# PCI_da_FPGA.net
KiCad netlist of a schematic drawn in EAGLE
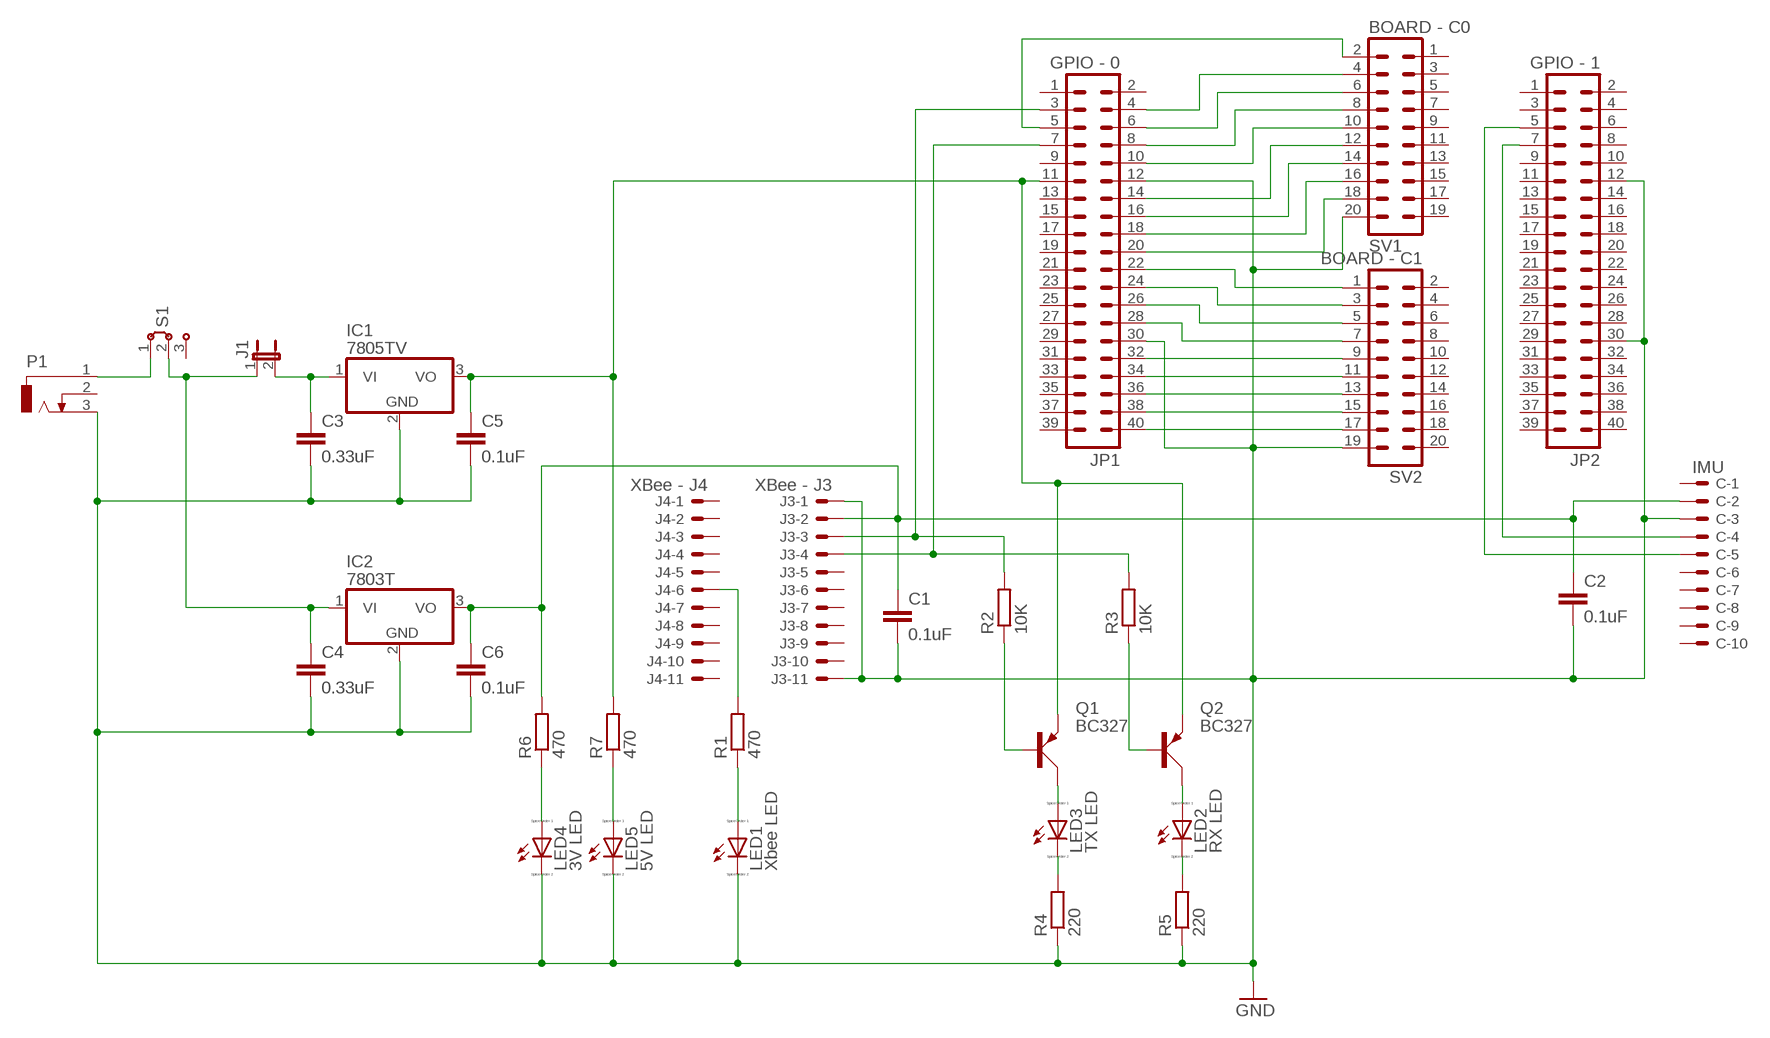
[diagram p0: schematic, sheet 1]

(export (version "E")
  (design (tool "Eeschema 10.0.6"))
  (components
    (comp (ref "C")
      (value "IMU")
      (footprint "eagle-import:22-23-2101")
      (fields (field (name "MF") "MOLEX") (field (name "MPN") "22-23-2101"))
      (libsource (lib "eagle-import") (part "22-23-2101"))
    )
    (comp (ref "C1")
      (value "0.1uF")
      (footprint "eagle-import:C5B2.5")
      (libsource (lib "eagle-import") (part "C5/2.5"))
    )
    (comp (ref "C2")
      (value "0.1uF")
      (footprint "eagle-import:C5B2.5")
      (libsource (lib "eagle-import") (part "C5/2.5"))
    )
    (comp (ref "C3")
      (value "0.33uF")
      (footprint "eagle-import:C5B2.5")
      (libsource (lib "eagle-import") (part "C5/2.5"))
    )
    (comp (ref "C4")
      (value "0.33uF")
      (footprint "eagle-import:C5B2.5")
      (libsource (lib "eagle-import") (part "C5/2.5"))
    )
    (comp (ref "C5")
      (value "0.1uF")
      (footprint "eagle-import:C5B2.5")
      (libsource (lib "eagle-import") (part "C5/2.5"))
    )
    (comp (ref "C6")
      (value "0.1uF")
      (footprint "eagle-import:C5B2.5")
      (libsource (lib "eagle-import") (part "C5/2.5"))
    )
    (comp (ref "IC1")
      (value "7805TV")
      (footprint "eagle-import:TO220V")
      (libsource (lib "eagle-import") (part "78TV05"))
    )
    (comp (ref "IC2")
      (value "7803T")
      (footprint "eagle-import:TO220V")
      (libsource (lib "eagle-import") (part "78TV05"))
    )
    (comp (ref "J1")
      (value "JP1E")
      (footprint "eagle-import:JP1")
      (libsource (lib "eagle-import") (part "JP1E"))
    )
    (comp (ref "J3")
      (value "XBee - J3")
      (footprint "eagle-import:22-23-2111")
      (fields (field (name "MF") "MOLEX") (field (name "MPN") "22-23-2111"))
      (libsource (lib "eagle-import") (part "22-23-2111"))
    )
    (comp (ref "J4")
      (value "XBee - J4")
      (footprint "eagle-import:22-23-2111")
      (fields (field (name "MF") "MOLEX") (field (name "MPN") "22-23-2111"))
      (libsource (lib "eagle-import") (part "22-23-2111"))
    )
    (comp (ref "JP1")
      (value "GPIO - 0")
      (footprint "eagle-import:ML40")
      (libsource (lib "eagle-import") (part "ML40"))
    )
    (comp (ref "JP2")
      (value "GPIO - 1")
      (footprint "eagle-import:ML40")
      (libsource (lib "eagle-import") (part "ML40"))
    )
    (comp (ref "LED1")
      (value "Xbee LED")
      (footprint "eagle-import:LED_LD260")
      (libsource (lib "eagle-import") (part "LED_ELD260"))
    )
    (comp (ref "LED2")
      (value "RX LED")
      (footprint "eagle-import:LED_LD260")
      (libsource (lib "eagle-import") (part "LED_ELD260"))
    )
    (comp (ref "LED3")
      (value "TX LED")
      (footprint "eagle-import:LED_LD260")
      (libsource (lib "eagle-import") (part "LED_ELD260"))
    )
    (comp (ref "LED4")
      (value "3V LED")
      (footprint "eagle-import:LED_LD260")
      (libsource (lib "eagle-import") (part "LED_ELD260"))
    )
    (comp (ref "LED5")
      (value "5V LED")
      (footprint "eagle-import:LED_LD260")
      (libsource (lib "eagle-import") (part "LED_ELD260"))
    )
    (comp (ref "P1")
      (value "DCJ0303")
      (footprint "eagle-import:DCJ0303")
      (libsource (lib "eagle-import") (part "DCJ0303"))
    )
    (comp (ref "Q1")
      (value "BC327")
      (footprint "eagle-import:SOT54A")
      (libsource (lib "eagle-import") (part "BC327"))
    )
    (comp (ref "Q2")
      (value "BC327")
      (footprint "eagle-import:SOT54A")
      (libsource (lib "eagle-import") (part "BC327"))
    )
    (comp (ref "R1")
      (value "470")
      (footprint "eagle-import:0207_10")
      (libsource (lib "eagle-import") (part "R-EU_0207/10"))
    )
    (comp (ref "R2")
      (value "10K")
      (footprint "eagle-import:0207_10")
      (libsource (lib "eagle-import") (part "R-EU_0207/10"))
    )
    (comp (ref "R3")
      (value "10K")
      (footprint "eagle-import:0207_10")
      (libsource (lib "eagle-import") (part "R-EU_0207/10"))
    )
    (comp (ref "R4")
      (value "220")
      (footprint "eagle-import:0207_10")
      (libsource (lib "eagle-import") (part "R-EU_0207/10"))
    )
    (comp (ref "R5")
      (value "220")
      (footprint "eagle-import:0207_10")
      (libsource (lib "eagle-import") (part "R-EU_0207/10"))
    )
    (comp (ref "R6")
      (value "470")
      (footprint "eagle-import:0207_10")
      (libsource (lib "eagle-import") (part "R-EU_0207/10"))
    )
    (comp (ref "R7")
      (value "470")
      (footprint "eagle-import:0207_10")
      (libsource (lib "eagle-import") (part "R-EU_0207/10"))
    )
    (comp (ref "S1")
      (value "J2X2MM")
      (footprint "eagle-import:04C")
      (libsource (lib "eagle-import") (part "J2X2MM"))
    )
    (comp (ref "SV1")
      (value "BOARD - C0")
      (footprint "eagle-import:ML20")
      (fields (field (name "OC_FARNELL") "unknown") (field (name "OC_NEWARK") "unknown"))
      (libsource (lib "eagle-import") (part "ML20"))
    )
    (comp (ref "SV2")
      (value "BOARD - C1")
      (footprint "eagle-import:ML20")
      (libsource (lib "eagle-import") (part "ML20"))
    )
  )
  (nets
    (net (code "1") (name "GND") (class "Default")
      (node (ref "C") (pin "3") (pinfunction "S_3") (pintype "passive"))
      (node (ref "C1") (pin "2") (pinfunction "2_2") (pintype "passive"))
      (node (ref "C2") (pin "2") (pinfunction "2_2") (pintype "passive"))
      (node (ref "C3") (pin "2") (pinfunction "2_2") (pintype "passive"))
      (node (ref "C4") (pin "2") (pinfunction "2_2") (pintype "passive"))
      (node (ref "C5") (pin "2") (pinfunction "2_2") (pintype "passive"))
      (node (ref "C6") (pin "2") (pinfunction "2_2") (pintype "passive"))
      (node (ref "IC1") (pin "2") (pinfunction "GND_2") (pintype "passive"))
      (node (ref "IC2") (pin "2") (pinfunction "GND_2") (pintype "passive"))
      (node (ref "J3") (pin "1") (pinfunction "S_1") (pintype "passive"))
      (node (ref "J3") (pin "11") (pinfunction "S_11") (pintype "passive"))
      (node (ref "JP1") (pin "12") (pinfunction "12_12") (pintype "passive"))
      (node (ref "JP1") (pin "30") (pinfunction "30_30") (pintype "passive"))
      (node (ref "JP2") (pin "12") (pinfunction "12_12") (pintype "passive"))
      (node (ref "JP2") (pin "30") (pinfunction "30_30") (pintype "passive"))
      (node (ref "LED1") (pin "K") (pinfunction "C_K") (pintype "passive"))
      (node (ref "LED4") (pin "K") (pinfunction "C_K") (pintype "passive"))
      (node (ref "LED5") (pin "K") (pinfunction "C_K") (pintype "passive"))
      (node (ref "P1") (pin "3") (pinfunction "3_3") (pintype "passive"))
      (node (ref "R4") (pin "1") (pinfunction "1_1") (pintype "passive"))
      (node (ref "R5") (pin "1") (pinfunction "1_1") (pintype "passive"))
      (node (ref "SV1") (pin "20") (pinfunction "20_20") (pintype "passive"))
      (node (ref "SV2") (pin "19") (pinfunction "19_19") (pintype "passive"))
    )
    (net (code "2") (name "Net-(CC-S)") (class "Default")
      (node (ref "C") (pin "2") (pinfunction "S_2") (pintype "passive"))
      (node (ref "C1") (pin "1") (pinfunction "1_1") (pintype "passive"))
      (node (ref "C2") (pin "1") (pinfunction "1_1") (pintype "passive"))
      (node (ref "C6") (pin "1") (pinfunction "1_1") (pintype "passive"))
      (node (ref "IC2") (pin "3") (pinfunction "VO_3") (pintype "passive"))
      (node (ref "J3") (pin "2") (pinfunction "S_2") (pintype "passive"))
      (node (ref "R6") (pin "2") (pinfunction "2_2") (pintype "passive"))
    )
    (net (code "3") (name "Net-(CE-S)") (class "Default")
      (node (ref "C") (pin "4") (pinfunction "S_4") (pintype "passive"))
      (node (ref "JP2") (pin "7") (pinfunction "7_7") (pintype "passive"))
    )
    (net (code "4") (name "Net-(CF-S)") (class "Default")
      (node (ref "C") (pin "5") (pinfunction "S_5") (pintype "passive"))
      (node (ref "JP2") (pin "5") (pinfunction "5_5") (pintype "passive"))
    )
    (net (code "5") (name "Net-(IC1-VI)") (class "Default")
      (node (ref "C3") (pin "1") (pinfunction "1_1") (pintype "passive"))
      (node (ref "IC1") (pin "1") (pinfunction "VI_1") (pintype "input"))
      (node (ref "J1") (pin "2") (pinfunction "2_2") (pintype "passive"))
    )
    (net (code "6") (name "Net-(IC1-VO)") (class "Default")
      (node (ref "C5") (pin "1") (pinfunction "1_1") (pintype "passive"))
      (node (ref "IC1") (pin "3") (pinfunction "VO_3") (pintype "passive"))
      (node (ref "JP1") (pin "11") (pinfunction "11_11") (pintype "passive"))
      (node (ref "Q1") (pin "E") (pinfunction "E_E") (pintype "passive"))
      (node (ref "Q2") (pin "E") (pinfunction "E_E") (pintype "passive"))
      (node (ref "R7") (pin "2") (pinfunction "2_2") (pintype "passive"))
    )
    (net (code "7") (name "Net-(IC2-VI)") (class "Default")
      (node (ref "C4") (pin "1") (pinfunction "1_1") (pintype "passive"))
      (node (ref "IC2") (pin "1") (pinfunction "VI_1") (pintype "input"))
      (node (ref "J1") (pin "1") (pinfunction "1_1") (pintype "passive"))
      (node (ref "S1") (pin "2") (pinfunction "2_2") (pintype "passive"))
    )
    (net (code "8") (name "Net-(J3E-S)") (class "Default")
      (node (ref "J3") (pin "3") (pinfunction "S_3") (pintype "passive"))
      (node (ref "JP1") (pin "3") (pinfunction "3_3") (pintype "passive"))
      (node (ref "R2") (pin "2") (pinfunction "2_2") (pintype "passive"))
    )
    (net (code "9") (name "Net-(J3F-S)") (class "Default")
      (node (ref "J3") (pin "4") (pinfunction "S_4") (pintype "passive"))
      (node (ref "JP1") (pin "7") (pinfunction "7_7") (pintype "passive"))
      (node (ref "R3") (pin "2") (pinfunction "2_2") (pintype "passive"))
    )
    (net (code "10") (name "Net-(J4H-S)") (class "Default")
      (node (ref "J4") (pin "6") (pinfunction "S_6") (pintype "passive"))
      (node (ref "R1") (pin "2") (pinfunction "2_2") (pintype "passive"))
    )
    (net (code "11") (name "Net-(JP1-Pad4)") (class "Default")
      (node (ref "JP1") (pin "4") (pinfunction "4_4") (pintype "passive"))
      (node (ref "SV1") (pin "4") (pinfunction "4_4") (pintype "passive"))
    )
    (net (code "12") (name "Net-(JP1-Pad5)") (class "Default")
      (node (ref "JP1") (pin "5") (pinfunction "5_5") (pintype "passive"))
      (node (ref "SV1") (pin "2") (pinfunction "2_2") (pintype "passive"))
    )
    (net (code "13") (name "Net-(JP1-Pad6)") (class "Default")
      (node (ref "JP1") (pin "6") (pinfunction "6_6") (pintype "passive"))
      (node (ref "SV1") (pin "6") (pinfunction "6_6") (pintype "passive"))
    )
    (net (code "14") (name "Net-(JP1-Pad8)") (class "Default")
      (node (ref "JP1") (pin "8") (pinfunction "8_8") (pintype "passive"))
      (node (ref "SV1") (pin "8") (pinfunction "8_8") (pintype "passive"))
    )
    (net (code "15") (name "Net-(JP1-Pad10)") (class "Default")
      (node (ref "JP1") (pin "10") (pinfunction "10_10") (pintype "passive"))
      (node (ref "SV1") (pin "10") (pinfunction "10_10") (pintype "passive"))
    )
    (net (code "16") (name "Net-(JP1-Pad14)") (class "Default")
      (node (ref "JP1") (pin "14") (pinfunction "14_14") (pintype "passive"))
      (node (ref "SV1") (pin "12") (pinfunction "12_12") (pintype "passive"))
    )
    (net (code "17") (name "Net-(JP1-Pad16)") (class "Default")
      (node (ref "JP1") (pin "16") (pinfunction "16_16") (pintype "passive"))
      (node (ref "SV1") (pin "14") (pinfunction "14_14") (pintype "passive"))
    )
    (net (code "18") (name "Net-(JP1-Pad18)") (class "Default")
      (node (ref "JP1") (pin "18") (pinfunction "18_18") (pintype "passive"))
      (node (ref "SV1") (pin "16") (pinfunction "16_16") (pintype "passive"))
    )
    (net (code "19") (name "Net-(JP1-Pad20)") (class "Default")
      (node (ref "JP1") (pin "20") (pinfunction "20_20") (pintype "passive"))
      (node (ref "SV1") (pin "18") (pinfunction "18_18") (pintype "passive"))
    )
    (net (code "20") (name "Net-(JP1-Pad22)") (class "Default")
      (node (ref "JP1") (pin "22") (pinfunction "22_22") (pintype "passive"))
      (node (ref "SV2") (pin "1") (pinfunction "1_1") (pintype "passive"))
    )
    (net (code "21") (name "Net-(JP1-Pad24)") (class "Default")
      (node (ref "JP1") (pin "24") (pinfunction "24_24") (pintype "passive"))
      (node (ref "SV2") (pin "3") (pinfunction "3_3") (pintype "passive"))
    )
    (net (code "22") (name "Net-(JP1-Pad26)") (class "Default")
      (node (ref "JP1") (pin "26") (pinfunction "26_26") (pintype "passive"))
      (node (ref "SV2") (pin "5") (pinfunction "5_5") (pintype "passive"))
    )
    (net (code "23") (name "Net-(JP1-Pad28)") (class "Default")
      (node (ref "JP1") (pin "28") (pinfunction "28_28") (pintype "passive"))
      (node (ref "SV2") (pin "7") (pinfunction "7_7") (pintype "passive"))
    )
    (net (code "24") (name "Net-(JP1-Pad32)") (class "Default")
      (node (ref "JP1") (pin "32") (pinfunction "32_32") (pintype "passive"))
      (node (ref "SV2") (pin "9") (pinfunction "9_9") (pintype "passive"))
    )
    (net (code "25") (name "Net-(JP1-Pad34)") (class "Default")
      (node (ref "JP1") (pin "34") (pinfunction "34_34") (pintype "passive"))
      (node (ref "SV2") (pin "11") (pinfunction "11_11") (pintype "passive"))
    )
    (net (code "26") (name "Net-(JP1-Pad36)") (class "Default")
      (node (ref "JP1") (pin "36") (pinfunction "36_36") (pintype "passive"))
      (node (ref "SV2") (pin "13") (pinfunction "13_13") (pintype "passive"))
    )
    (net (code "27") (name "Net-(JP1-Pad38)") (class "Default")
      (node (ref "JP1") (pin "38") (pinfunction "38_38") (pintype "passive"))
      (node (ref "SV2") (pin "15") (pinfunction "15_15") (pintype "passive"))
    )
    (net (code "28") (name "Net-(JP1-Pad40)") (class "Default")
      (node (ref "JP1") (pin "40") (pinfunction "40_40") (pintype "passive"))
      (node (ref "SV2") (pin "17") (pinfunction "17_17") (pintype "passive"))
    )
    (net (code "29") (name "Net-(LED1-PadA)") (class "Default")
      (node (ref "LED1") (pin "A") (pinfunction "A_A") (pintype "passive"))
      (node (ref "R1") (pin "1") (pinfunction "1_1") (pintype "passive"))
    )
    (net (code "30") (name "Net-(LED2-C)") (class "Default")
      (node (ref "LED2") (pin "K") (pinfunction "C_K") (pintype "passive"))
      (node (ref "R5") (pin "2") (pinfunction "2_2") (pintype "passive"))
    )
    (net (code "31") (name "Net-(LED2-PadA)") (class "Default")
      (node (ref "LED2") (pin "A") (pinfunction "A_A") (pintype "passive"))
      (node (ref "Q2") (pin "C") (pinfunction "C_C") (pintype "passive"))
    )
    (net (code "32") (name "Net-(LED3-C)") (class "Default")
      (node (ref "LED3") (pin "K") (pinfunction "C_K") (pintype "passive"))
      (node (ref "R4") (pin "2") (pinfunction "2_2") (pintype "passive"))
    )
    (net (code "33") (name "Net-(LED3-PadA)") (class "Default")
      (node (ref "LED3") (pin "A") (pinfunction "A_A") (pintype "passive"))
      (node (ref "Q1") (pin "C") (pinfunction "C_C") (pintype "passive"))
    )
    (net (code "34") (name "Net-(LED4-PadA)") (class "Default")
      (node (ref "LED4") (pin "A") (pinfunction "A_A") (pintype "passive"))
      (node (ref "R6") (pin "1") (pinfunction "1_1") (pintype "passive"))
    )
    (net (code "35") (name "Net-(LED5-PadA)") (class "Default")
      (node (ref "LED5") (pin "A") (pinfunction "A_A") (pintype "passive"))
      (node (ref "R7") (pin "1") (pinfunction "1_1") (pintype "passive"))
    )
    (net (code "36") (name "Net-(P1-Pad1)") (class "Default")
      (node (ref "P1") (pin "1") (pinfunction "1_1") (pintype "passive"))
      (node (ref "S1") (pin "1") (pinfunction "1_1") (pintype "passive"))
    )
    (net (code "37") (name "Net-(Q1-PadB)") (class "Default")
      (node (ref "Q1") (pin "B") (pinfunction "B_B") (pintype "passive"))
      (node (ref "R2") (pin "1") (pinfunction "1_1") (pintype "passive"))
    )
    (net (code "38") (name "Net-(Q2-PadB)") (class "Default")
      (node (ref "Q2") (pin "B") (pinfunction "B_B") (pintype "passive"))
      (node (ref "R3") (pin "1") (pinfunction "1_1") (pintype "passive"))
    )
    (net (code "39") (name "unconnected-(CA-S-Pad1)") (class "Default")
      (node (ref "C") (pin "1") (pinfunction "S_1") (pintype "passive"))
    )
    (net (code "40") (name "unconnected-(CB-S-Pad10)") (class "Default")
      (node (ref "C") (pin "10") (pinfunction "S_10") (pintype "passive"))
    )
    (net (code "41") (name "unconnected-(CG-S-Pad6)") (class "Default")
      (node (ref "C") (pin "6") (pinfunction "S_6") (pintype "passive"))
    )
    (net (code "42") (name "unconnected-(CH-S-Pad7)") (class "Default")
      (node (ref "C") (pin "7") (pinfunction "S_7") (pintype "passive"))
    )
    (net (code "43") (name "unconnected-(CI-S-Pad8)") (class "Default")
      (node (ref "C") (pin "8") (pinfunction "S_8") (pintype "passive"))
    )
    (net (code "44") (name "unconnected-(CJ-S-Pad9)") (class "Default")
      (node (ref "C") (pin "9") (pinfunction "S_9") (pintype "passive"))
    )
    (net (code "45") (name "unconnected-(J3B-S-Pad10)") (class "Default")
      (node (ref "J3") (pin "10") (pinfunction "S_10") (pintype "passive"))
    )
    (net (code "46") (name "unconnected-(J3G-S-Pad5)") (class "Default")
      (node (ref "J3") (pin "5") (pinfunction "S_5") (pintype "passive"))
    )
    (net (code "47") (name "unconnected-(J3H-S-Pad6)") (class "Default")
      (node (ref "J3") (pin "6") (pinfunction "S_6") (pintype "passive"))
    )
    (net (code "48") (name "unconnected-(J3I-S-Pad7)") (class "Default")
      (node (ref "J3") (pin "7") (pinfunction "S_7") (pintype "passive"))
    )
    (net (code "49") (name "unconnected-(J3J-S-Pad8)") (class "Default")
      (node (ref "J3") (pin "8") (pinfunction "S_8") (pintype "passive"))
    )
    (net (code "50") (name "unconnected-(J3K-S-Pad9)") (class "Default")
      (node (ref "J3") (pin "9") (pinfunction "S_9") (pintype "passive"))
    )
    (net (code "51") (name "unconnected-(J4A-S-Pad1)") (class "Default")
      (node (ref "J4") (pin "1") (pinfunction "S_1") (pintype "passive"))
    )
    (net (code "52") (name "unconnected-(J4B-S-Pad10)") (class "Default")
      (node (ref "J4") (pin "10") (pinfunction "S_10") (pintype "passive"))
    )
    (net (code "53") (name "unconnected-(J4C-S-Pad11)") (class "Default")
      (node (ref "J4") (pin "11") (pinfunction "S_11") (pintype "passive"))
    )
    (net (code "54") (name "unconnected-(J4D-S-Pad2)") (class "Default")
      (node (ref "J4") (pin "2") (pinfunction "S_2") (pintype "passive"))
    )
    (net (code "55") (name "unconnected-(J4E-S-Pad3)") (class "Default")
      (node (ref "J4") (pin "3") (pinfunction "S_3") (pintype "passive"))
    )
    (net (code "56") (name "unconnected-(J4F-S-Pad4)") (class "Default")
      (node (ref "J4") (pin "4") (pinfunction "S_4") (pintype "passive"))
    )
    (net (code "57") (name "unconnected-(J4G-S-Pad5)") (class "Default")
      (node (ref "J4") (pin "5") (pinfunction "S_5") (pintype "passive"))
    )
    (net (code "58") (name "unconnected-(J4I-S-Pad7)") (class "Default")
      (node (ref "J4") (pin "7") (pinfunction "S_7") (pintype "passive"))
    )
    (net (code "59") (name "unconnected-(J4J-S-Pad8)") (class "Default")
      (node (ref "J4") (pin "8") (pinfunction "S_8") (pintype "passive"))
    )
    (net (code "60") (name "unconnected-(J4K-S-Pad9)") (class "Default")
      (node (ref "J4") (pin "9") (pinfunction "S_9") (pintype "passive"))
    )
    (net (code "61") (name "unconnected-(JP1-Pad1)") (class "Default")
      (node (ref "JP1") (pin "1") (pinfunction "1_1") (pintype "passive"))
    )
    (net (code "62") (name "unconnected-(JP1-Pad2)") (class "Default")
      (node (ref "JP1") (pin "2") (pinfunction "2_2") (pintype "passive"))
    )
    (net (code "63") (name "unconnected-(JP1-Pad9)") (class "Default")
      (node (ref "JP1") (pin "9") (pinfunction "9_9") (pintype "passive"))
    )
    (net (code "64") (name "unconnected-(JP1-Pad13)") (class "Default")
      (node (ref "JP1") (pin "13") (pinfunction "13_13") (pintype "passive"))
    )
    (net (code "65") (name "unconnected-(JP1-Pad15)") (class "Default")
      (node (ref "JP1") (pin "15") (pinfunction "15_15") (pintype "passive"))
    )
    (net (code "66") (name "unconnected-(JP1-Pad17)") (class "Default")
      (node (ref "JP1") (pin "17") (pinfunction "17_17") (pintype "passive"))
    )
    (net (code "67") (name "unconnected-(JP1-Pad19)") (class "Default")
      (node (ref "JP1") (pin "19") (pinfunction "19_19") (pintype "passive"))
    )
    (net (code "68") (name "unconnected-(JP1-Pad21)") (class "Default")
      (node (ref "JP1") (pin "21") (pinfunction "21_21") (pintype "passive"))
    )
    (net (code "69") (name "unconnected-(JP1-Pad23)") (class "Default")
      (node (ref "JP1") (pin "23") (pinfunction "23_23") (pintype "passive"))
    )
    (net (code "70") (name "unconnected-(JP1-Pad25)") (class "Default")
      (node (ref "JP1") (pin "25") (pinfunction "25_25") (pintype "passive"))
    )
    (net (code "71") (name "unconnected-(JP1-Pad27)") (class "Default")
      (node (ref "JP1") (pin "27") (pinfunction "27_27") (pintype "passive"))
    )
    (net (code "72") (name "unconnected-(JP1-Pad29)") (class "Default")
      (node (ref "JP1") (pin "29") (pinfunction "29_29") (pintype "passive"))
    )
    (net (code "73") (name "unconnected-(JP1-Pad31)") (class "Default")
      (node (ref "JP1") (pin "31") (pinfunction "31_31") (pintype "passive"))
    )
    (net (code "74") (name "unconnected-(JP1-Pad33)") (class "Default")
      (node (ref "JP1") (pin "33") (pinfunction "33_33") (pintype "passive"))
    )
    (net (code "75") (name "unconnected-(JP1-Pad35)") (class "Default")
      (node (ref "JP1") (pin "35") (pinfunction "35_35") (pintype "passive"))
    )
    (net (code "76") (name "unconnected-(JP1-Pad37)") (class "Default")
      (node (ref "JP1") (pin "37") (pinfunction "37_37") (pintype "passive"))
    )
    (net (code "77") (name "unconnected-(JP1-Pad39)") (class "Default")
      (node (ref "JP1") (pin "39") (pinfunction "39_39") (pintype "passive"))
    )
    (net (code "78") (name "unconnected-(JP2-Pad1)") (class "Default")
      (node (ref "JP2") (pin "1") (pinfunction "1_1") (pintype "passive"))
    )
    (net (code "79") (name "unconnected-(JP2-Pad2)") (class "Default")
      (node (ref "JP2") (pin "2") (pinfunction "2_2") (pintype "passive"))
    )
    (net (code "80") (name "unconnected-(JP2-Pad3)") (class "Default")
      (node (ref "JP2") (pin "3") (pinfunction "3_3") (pintype "passive"))
    )
    (net (code "81") (name "unconnected-(JP2-Pad4)") (class "Default")
      (node (ref "JP2") (pin "4") (pinfunction "4_4") (pintype "passive"))
    )
    (net (code "82") (name "unconnected-(JP2-Pad6)") (class "Default")
      (node (ref "JP2") (pin "6") (pinfunction "6_6") (pintype "passive"))
    )
    (net (code "83") (name "unconnected-(JP2-Pad8)") (class "Default")
      (node (ref "JP2") (pin "8") (pinfunction "8_8") (pintype "passive"))
    )
    (net (code "84") (name "unconnected-(JP2-Pad9)") (class "Default")
      (node (ref "JP2") (pin "9") (pinfunction "9_9") (pintype "passive"))
    )
    (net (code "85") (name "unconnected-(JP2-Pad10)") (class "Default")
      (node (ref "JP2") (pin "10") (pinfunction "10_10") (pintype "passive"))
    )
    (net (code "86") (name "unconnected-(JP2-Pad11)") (class "Default")
      (node (ref "JP2") (pin "11") (pinfunction "11_11") (pintype "passive"))
    )
    (net (code "87") (name "unconnected-(JP2-Pad13)") (class "Default")
      (node (ref "JP2") (pin "13") (pinfunction "13_13") (pintype "passive"))
    )
    (net (code "88") (name "unconnected-(JP2-Pad14)") (class "Default")
      (node (ref "JP2") (pin "14") (pinfunction "14_14") (pintype "passive"))
    )
    (net (code "89") (name "unconnected-(JP2-Pad15)") (class "Default")
      (node (ref "JP2") (pin "15") (pinfunction "15_15") (pintype "passive"))
    )
    (net (code "90") (name "unconnected-(JP2-Pad16)") (class "Default")
      (node (ref "JP2") (pin "16") (pinfunction "16_16") (pintype "passive"))
    )
    (net (code "91") (name "unconnected-(JP2-Pad17)") (class "Default")
      (node (ref "JP2") (pin "17") (pinfunction "17_17") (pintype "passive"))
    )
    (net (code "92") (name "unconnected-(JP2-Pad18)") (class "Default")
      (node (ref "JP2") (pin "18") (pinfunction "18_18") (pintype "passive"))
    )
    (net (code "93") (name "unconnected-(JP2-Pad19)") (class "Default")
      (node (ref "JP2") (pin "19") (pinfunction "19_19") (pintype "passive"))
    )
    (net (code "94") (name "unconnected-(JP2-Pad20)") (class "Default")
      (node (ref "JP2") (pin "20") (pinfunction "20_20") (pintype "passive"))
    )
    (net (code "95") (name "unconnected-(JP2-Pad21)") (class "Default")
      (node (ref "JP2") (pin "21") (pinfunction "21_21") (pintype "passive"))
    )
    (net (code "96") (name "unconnected-(JP2-Pad22)") (class "Default")
      (node (ref "JP2") (pin "22") (pinfunction "22_22") (pintype "passive"))
    )
    (net (code "97") (name "unconnected-(JP2-Pad23)") (class "Default")
      (node (ref "JP2") (pin "23") (pinfunction "23_23") (pintype "passive"))
    )
    (net (code "98") (name "unconnected-(JP2-Pad24)") (class "Default")
      (node (ref "JP2") (pin "24") (pinfunction "24_24") (pintype "passive"))
    )
    (net (code "99") (name "unconnected-(JP2-Pad25)") (class "Default")
      (node (ref "JP2") (pin "25") (pinfunction "25_25") (pintype "passive"))
    )
    (net (code "100") (name "unconnected-(JP2-Pad26)") (class "Default")
      (node (ref "JP2") (pin "26") (pinfunction "26_26") (pintype "passive"))
    )
    (net (code "101") (name "unconnected-(JP2-Pad27)") (class "Default")
      (node (ref "JP2") (pin "27") (pinfunction "27_27") (pintype "passive"))
    )
    (net (code "102") (name "unconnected-(JP2-Pad28)") (class "Default")
      (node (ref "JP2") (pin "28") (pinfunction "28_28") (pintype "passive"))
    )
    (net (code "103") (name "unconnected-(JP2-Pad29)") (class "Default")
      (node (ref "JP2") (pin "29") (pinfunction "29_29") (pintype "passive"))
    )
    (net (code "104") (name "unconnected-(JP2-Pad31)") (class "Default")
      (node (ref "JP2") (pin "31") (pinfunction "31_31") (pintype "passive"))
    )
    (net (code "105") (name "unconnected-(JP2-Pad32)") (class "Default")
      (node (ref "JP2") (pin "32") (pinfunction "32_32") (pintype "passive"))
    )
    (net (code "106") (name "unconnected-(JP2-Pad33)") (class "Default")
      (node (ref "JP2") (pin "33") (pinfunction "33_33") (pintype "passive"))
    )
    (net (code "107") (name "unconnected-(JP2-Pad34)") (class "Default")
      (node (ref "JP2") (pin "34") (pinfunction "34_34") (pintype "passive"))
    )
    (net (code "108") (name "unconnected-(JP2-Pad35)") (class "Default")
      (node (ref "JP2") (pin "35") (pinfunction "35_35") (pintype "passive"))
    )
    (net (code "109") (name "unconnected-(JP2-Pad36)") (class "Default")
      (node (ref "JP2") (pin "36") (pinfunction "36_36") (pintype "passive"))
    )
    (net (code "110") (name "unconnected-(JP2-Pad37)") (class "Default")
      (node (ref "JP2") (pin "37") (pinfunction "37_37") (pintype "passive"))
    )
    (net (code "111") (name "unconnected-(JP2-Pad38)") (class "Default")
      (node (ref "JP2") (pin "38") (pinfunction "38_38") (pintype "passive"))
    )
    (net (code "112") (name "unconnected-(JP2-Pad39)") (class "Default")
      (node (ref "JP2") (pin "39") (pinfunction "39_39") (pintype "passive"))
    )
    (net (code "113") (name "unconnected-(JP2-Pad40)") (class "Default")
      (node (ref "JP2") (pin "40") (pinfunction "40_40") (pintype "passive"))
    )
    (net (code "114") (name "unconnected-(P1-Pad2)") (class "Default")
      (node (ref "P1") (pin "2") (pinfunction "2_2") (pintype "passive"))
    )
    (net (code "115") (name "unconnected-(S1-Pad3)") (class "Default")
      (node (ref "S1") (pin "3") (pinfunction "3_3") (pintype "passive"))
    )
    (net (code "116") (name "unconnected-(SV1-Pad1)") (class "Default")
      (node (ref "SV1") (pin "1") (pinfunction "1_1") (pintype "passive"))
    )
    (net (code "117") (name "unconnected-(SV1-Pad3)") (class "Default")
      (node (ref "SV1") (pin "3") (pinfunction "3_3") (pintype "passive"))
    )
    (net (code "118") (name "unconnected-(SV1-Pad5)") (class "Default")
      (node (ref "SV1") (pin "5") (pinfunction "5_5") (pintype "passive"))
    )
    (net (code "119") (name "unconnected-(SV1-Pad7)") (class "Default")
      (node (ref "SV1") (pin "7") (pinfunction "7_7") (pintype "passive"))
    )
    (net (code "120") (name "unconnected-(SV1-Pad9)") (class "Default")
      (node (ref "SV1") (pin "9") (pinfunction "9_9") (pintype "passive"))
    )
    (net (code "121") (name "unconnected-(SV1-Pad11)") (class "Default")
      (node (ref "SV1") (pin "11") (pinfunction "11_11") (pintype "passive"))
    )
    (net (code "122") (name "unconnected-(SV1-Pad13)") (class "Default")
      (node (ref "SV1") (pin "13") (pinfunction "13_13") (pintype "passive"))
    )
    (net (code "123") (name "unconnected-(SV1-Pad15)") (class "Default")
      (node (ref "SV1") (pin "15") (pinfunction "15_15") (pintype "passive"))
    )
    (net (code "124") (name "unconnected-(SV1-Pad17)") (class "Default")
      (node (ref "SV1") (pin "17") (pinfunction "17_17") (pintype "passive"))
    )
    (net (code "125") (name "unconnected-(SV1-Pad19)") (class "Default")
      (node (ref "SV1") (pin "19") (pinfunction "19_19") (pintype "passive"))
    )
    (net (code "126") (name "unconnected-(SV2-Pad2)") (class "Default")
      (node (ref "SV2") (pin "2") (pinfunction "2_2") (pintype "passive"))
    )
    (net (code "127") (name "unconnected-(SV2-Pad4)") (class "Default")
      (node (ref "SV2") (pin "4") (pinfunction "4_4") (pintype "passive"))
    )
    (net (code "128") (name "unconnected-(SV2-Pad6)") (class "Default")
      (node (ref "SV2") (pin "6") (pinfunction "6_6") (pintype "passive"))
    )
    (net (code "129") (name "unconnected-(SV2-Pad8)") (class "Default")
      (node (ref "SV2") (pin "8") (pinfunction "8_8") (pintype "passive"))
    )
    (net (code "130") (name "unconnected-(SV2-Pad10)") (class "Default")
      (node (ref "SV2") (pin "10") (pinfunction "10_10") (pintype "passive"))
    )
    (net (code "131") (name "unconnected-(SV2-Pad12)") (class "Default")
      (node (ref "SV2") (pin "12") (pinfunction "12_12") (pintype "passive"))
    )
    (net (code "132") (name "unconnected-(SV2-Pad14)") (class "Default")
      (node (ref "SV2") (pin "14") (pinfunction "14_14") (pintype "passive"))
    )
    (net (code "133") (name "unconnected-(SV2-Pad16)") (class "Default")
      (node (ref "SV2") (pin "16") (pinfunction "16_16") (pintype "passive"))
    )
    (net (code "134") (name "unconnected-(SV2-Pad18)") (class "Default")
      (node (ref "SV2") (pin "18") (pinfunction "18_18") (pintype "passive"))
    )
    (net (code "135") (name "unconnected-(SV2-Pad20)") (class "Default")
      (node (ref "SV2") (pin "20") (pinfunction "20_20") (pintype "passive"))
    )
  )
)
